# CANTransiver.net
KiCad netlist of a schematic drawn in Altium Designer
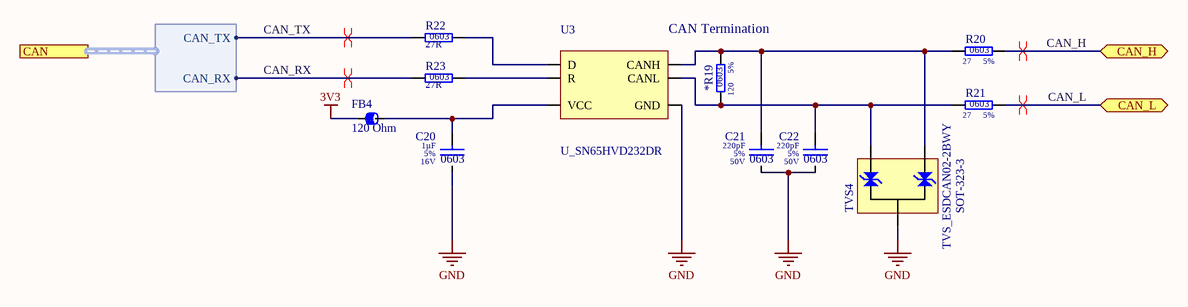
[diagram p0: CANTransiver.SchDoc]

(export (version "E")
  (design (tool "Eeschema 10.0.6"))
  (components
    (comp (ref "*R19")
      (value "R_120_0603_5")
      (footprint "0603_HandSold_Resistor")
      (fields
        (field (name "TOLERANCE") "5%")
        (field (name "RESISTANCE") "120")
        (field (name "CASE/PACKAGE") "0603")
        (field (name "POWER") "100mW")
      )
      (libsource (lib "Altium Concord Pro on A365") (part "Resistor"))
    )
    (comp (ref "C20")
      (value "1µF")
      (footprint "0603_HandSold_Capacitor")
      (description "C_1u_16V_0603_5")
      (fields
        (field (name "TOLERANCE") "5%")
        (field (name "VOLTAGE RATING") "16V")
        (field (name "CASE/PACKAGE") "0603")
      )
      (libsource (lib "Altium Concord Pro on A365") (part "Capacitor"))
    )
    (comp (ref "C21")
      (value "220pF")
      (footprint "0603_HandSold_Capacitor")
      (description "C_220p_50V_0603_5")
      (fields
        (field (name "TOLERANCE") "5%")
        (field (name "VOLTAGE RATING") "50V")
        (field (name "CASE/PACKAGE") "0603")
      )
      (libsource (lib "Altium Concord Pro on A365") (part "Capacitor"))
    )
    (comp (ref "C22")
      (value "220pF")
      (footprint "0603_HandSold_Capacitor")
      (description "C_220p_50V_0603_5")
      (fields
        (field (name "TOLERANCE") "5%")
        (field (name "VOLTAGE RATING") "50V")
        (field (name "CASE/PACKAGE") "0603")
      )
      (libsource (lib "Altium Concord Pro on A365") (part "Capacitor"))
    )
    (comp (ref "FB4")
      (value "FB_BLM21PG121SN1D")
      (footprint "0805_FB")
      (description "Ferrite Beads 120 OHM 25% Alternate Sizing Guide Below")
      (fields (field (name "IMPEDANCE") "120 Ohm"))
      (libsource (lib "Altium Concord Pro on A365") (part "FerriteBead"))
    )
    (comp (ref "R20")
      (value "R_27_0603_5")
      (footprint "0603_HandSold_Resistor")
      (fields
        (field (name "TOLERANCE") "5%")
        (field (name "RESISTANCE") "27")
        (field (name "CASE/PACKAGE") "0603")
        (field (name "POWER") "100mW")
      )
      (libsource (lib "Altium Concord Pro on A365") (part "Resistor"))
    )
    (comp (ref "R21")
      (value "R_27_0603_5")
      (footprint "0603_HandSold_Resistor")
      (fields
        (field (name "TOLERANCE") "5%")
        (field (name "RESISTANCE") "27")
        (field (name "CASE/PACKAGE") "0603")
        (field (name "POWER") "100mW")
      )
      (libsource (lib "Altium Concord Pro on A365") (part "Resistor"))
    )
    (comp (ref "R22")
      (value "27R")
      (footprint "R_0603_1608")
      (fields
        (field (name "SCH_FOOTPRINT") "0603")
        (field (name "PART NUMBER") "R_27R_0603_1")
        (field (name "VOLTAGE") "75V")
        (field (name "POWER") "330mW")
      )
      (libsource (lib "Library") (part "R"))
    )
    (comp (ref "R23")
      (value "27R")
      (footprint "R_0603_1608")
      (fields
        (field (name "SCH_FOOTPRINT") "0603")
        (field (name "PART NUMBER") "R_27R_0603_1")
        (field (name "VOLTAGE") "75V")
        (field (name "POWER") "330mW")
      )
      (libsource (lib "Library") (part "R"))
    )
    (comp (ref "TVS4")
      (value "TVS_ESDCAN02-2BWY")
      (footprint "SOT-323-3")
      (description "Diode; 2x TVS; 26.5V 28.5V 44V")
      (fields (field (name "CASE/PACKAGE") "SOT-323-3"))
      (libsource (lib "Altium Concord Pro on A365") (part "TVS 2 diodes with common ground"))
    )
    (comp (ref "U3")
      (value "U_SN65HVD232DR")
      (footprint "SOIC8")
      (description "Transceiver; CAN; SN65HVD232; 1Mb/s; 3.3V SMT")
      (libsource (lib "Altium Concord Pro on A365") (part "SN65HVD232 Series"))
    )
  )
  (nets
    (net (code "2") (name "/CAN_H") (class "Default")
      (node (ref "R20") (pin "2") (pinfunction "2_2") (pintype "passive"))
    )
    (net (code "3") (name "/CAN_L") (class "Default")
      (node (ref "R21") (pin "2") (pinfunction "2_2") (pintype "passive"))
    )
    (net (code "4") (name "/CAN_RX") (class "Default")
      (node (ref "R23") (pin "1") (pinfunction "1_1") (pintype "passive"))
    )
    (net (code "5") (name "/CAN_TX") (class "Default")
      (node (ref "R22") (pin "1") (pinfunction "1_1") (pintype "passive"))
    )
    (net (code "7") (name "3V3") (class "Default")
      (node (ref "FB4") (pin "1") (pinfunction "1_1") (pintype "passive"))
    )
    (net (code "8") (name "GND") (class "Default")
      (node (ref "C20") (pin "2") (pinfunction "2_2") (pintype "passive"))
      (node (ref "C21") (pin "2") (pinfunction "2_2") (pintype "passive"))
      (node (ref "C22") (pin "2") (pinfunction "2_2") (pintype "passive"))
      (node (ref "TVS4") (pin "3") (pinfunction "3_3") (pintype "passive"))
      (node (ref "U3") (pin "2") (pinfunction "GND_2") (pintype "passive"))
    )
    (net (code "9") (name "Net-(U3-CANH)") (class "Default")
      (node (ref "*R19") (pin "2") (pinfunction "2_2") (pintype "passive"))
      (node (ref "C21") (pin "1") (pinfunction "1_1") (pintype "passive"))
      (node (ref "R20") (pin "1") (pinfunction "1_1") (pintype "passive"))
      (node (ref "TVS4") (pin "1") (pinfunction "1_1") (pintype "passive"))
      (node (ref "U3") (pin "7") (pinfunction "CANH_7") (pintype "passive"))
    )
    (net (code "10") (name "Net-(U3-CANL)") (class "Default")
      (node (ref "*R19") (pin "1") (pinfunction "1_1") (pintype "passive"))
      (node (ref "C22") (pin "1") (pinfunction "1_1") (pintype "passive"))
      (node (ref "R21") (pin "1") (pinfunction "1_1") (pintype "passive"))
      (node (ref "TVS4") (pin "2") (pinfunction "2_2") (pintype "passive"))
      (node (ref "U3") (pin "6") (pinfunction "CANL_6") (pintype "passive"))
    )
    (net (code "11") (name "Net-(U3-D)") (class "Default")
      (node (ref "R22") (pin "2") (pinfunction "2_2") (pintype "passive"))
      (node (ref "U3") (pin "1") (pinfunction "D_1") (pintype "passive"))
    )
    (net (code "12") (name "Net-(U3-R)") (class "Default")
      (node (ref "R23") (pin "2") (pinfunction "2_2") (pintype "passive"))
      (node (ref "U3") (pin "4") (pinfunction "R_4") (pintype "passive"))
    )
    (net (code "13") (name "Net-(U3-VCC)") (class "Default")
      (node (ref "C20") (pin "1") (pinfunction "1_1") (pintype "passive"))
      (node (ref "FB4") (pin "2") (pinfunction "2_2") (pintype "passive"))
      (node (ref "U3") (pin "3") (pinfunction "VCC_3") (pintype "passive"))
    )
  )
)
